# 7seg-2_54-new.net
KiCad netlist of a schematic drawn in EAGLE
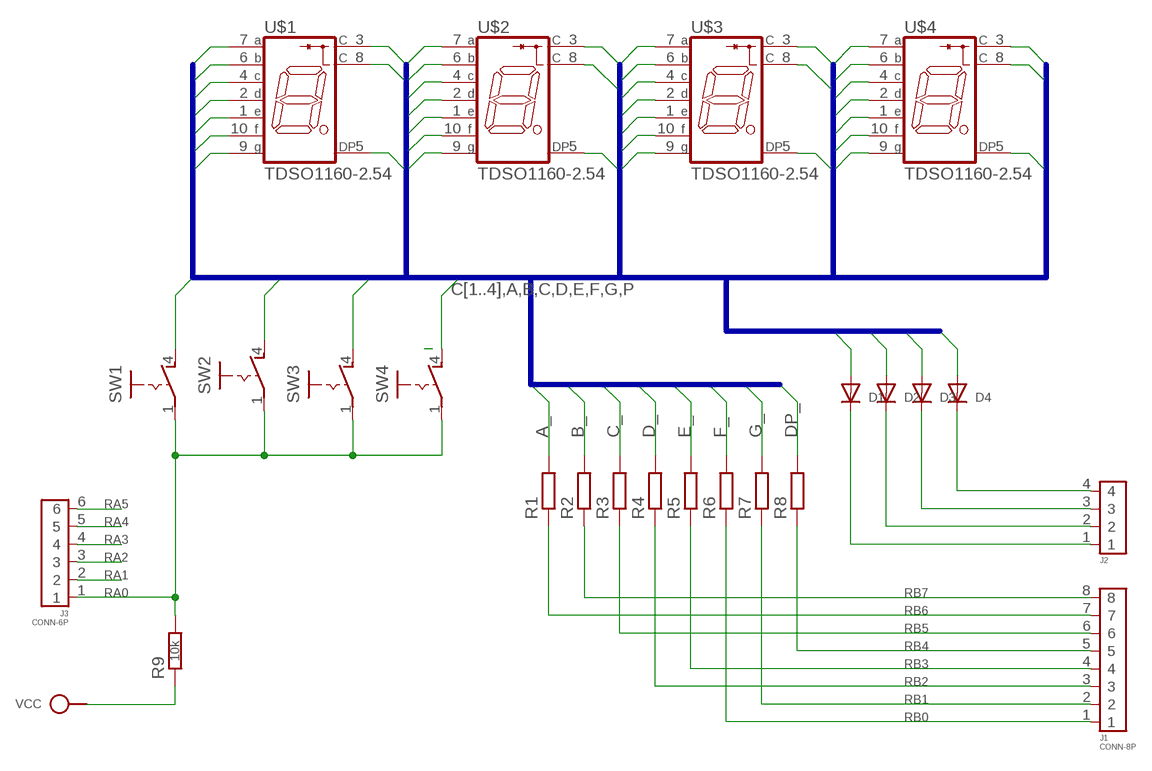
[diagram p0: schematic, sheet 1]

(export (version "E")
  (design (tool "Eeschema 10.0.6"))
  (components
    (comp (ref "D1")
      (value "1N414834-2,5")
      (footprint "eagle-import:DO34-2,5")
      (libsource (lib "eagle-import") (part "1N414834-2,5"))
    )
    (comp (ref "D2")
      (value "1N414834-2,5")
      (footprint "eagle-import:DO34-2,5")
      (libsource (lib "eagle-import") (part "1N414834-2,5"))
    )
    (comp (ref "D3")
      (value "1N414834-2,5")
      (footprint "eagle-import:DO34-2,5")
      (libsource (lib "eagle-import") (part "1N414834-2,5"))
    )
    (comp (ref "D4")
      (value "1N414834-2,5")
      (footprint "eagle-import:DO34-2,5")
      (libsource (lib "eagle-import") (part "1N414834-2,5"))
    )
    (comp (ref "J1")
      (value "CONN-8P")
      (footprint "eagle-import:CONN-8P")
      (libsource (lib "eagle-import") (part "CONN-8P"))
    )
    (comp (ref "J2")
      (value "CONN-4P-4P")
      (footprint "eagle-import:CONN-4P")
      (libsource (lib "eagle-import") (part "CONN-4P-4P"))
    )
    (comp (ref "J3")
      (value "CONN-6P")
      (footprint "eagle-import:CONN-6P")
      (libsource (lib "eagle-import") (part "CONN-6P"))
    )
    (comp (ref "R1")
      (value "R0202/5-V")
      (footprint "eagle-import:0202_5-V")
      (libsource (lib "eagle-import") (part "R0202/5-V"))
    )
    (comp (ref "R2")
      (value "R0202/5-V")
      (footprint "eagle-import:0202_5-V")
      (libsource (lib "eagle-import") (part "R0202/5-V"))
    )
    (comp (ref "R3")
      (value "R0202/5-V")
      (footprint "eagle-import:0202_5-V")
      (libsource (lib "eagle-import") (part "R0202/5-V"))
    )
    (comp (ref "R4")
      (value "R0202/5-V")
      (footprint "eagle-import:0202_5-V")
      (libsource (lib "eagle-import") (part "R0202/5-V"))
    )
    (comp (ref "R5")
      (value "R0202/5-V")
      (footprint "eagle-import:0202_5-V")
      (libsource (lib "eagle-import") (part "R0202/5-V"))
    )
    (comp (ref "R6")
      (value "R0202/5-V")
      (footprint "eagle-import:0202_5-V")
      (libsource (lib "eagle-import") (part "R0202/5-V"))
    )
    (comp (ref "R7")
      (value "R0202/5-V")
      (footprint "eagle-import:0202_5-V")
      (libsource (lib "eagle-import") (part "R0202/5-V"))
    )
    (comp (ref "R8")
      (value "R0202/5-V")
      (footprint "eagle-import:0202_5-V")
      (libsource (lib "eagle-import") (part "R0202/5-V"))
    )
    (comp (ref "R9")
      (value "10k")
      (footprint "eagle-import:0202_5-V")
      (libsource (lib "eagle-import") (part "R0202/5-V"))
    )
    (comp (ref "SW1")
      (value "PB-1P-1T2P1T-2X3")
      (footprint "eagle-import:PB-2P1T-2X3")
      (libsource (lib "eagle-import") (part "PB-1P-1T2P1T-2X3"))
    )
    (comp (ref "SW2")
      (value "PB-1P-1T2P1T-2X3")
      (footprint "eagle-import:PB-2P1T-2X3")
      (libsource (lib "eagle-import") (part "PB-1P-1T2P1T-2X3"))
    )
    (comp (ref "SW3")
      (value "PB-1P-1T2P1T-2X3")
      (footprint "eagle-import:PB-2P1T-2X3")
      (libsource (lib "eagle-import") (part "PB-1P-1T2P1T-2X3"))
    )
    (comp (ref "SW4")
      (value "PB-1P-1T2P1T-2X3")
      (footprint "eagle-import:PB-2P1T-2X3")
      (libsource (lib "eagle-import") (part "PB-1P-1T2P1T-2X3"))
    )
    (comp (ref "U$1")
      (value "TDSO1160-2.54")
      (footprint "eagle-import:TDSX1150-2.54")
      (libsource (lib "eagle-import") (part "TDSO1160-2.54"))
    )
    (comp (ref "U$2")
      (value "TDSO1160-2.54")
      (footprint "eagle-import:TDSX1150-2.54")
      (libsource (lib "eagle-import") (part "TDSO1160-2.54"))
    )
    (comp (ref "U$3")
      (value "TDSO1160-2.54")
      (footprint "eagle-import:TDSX1150-2.54")
      (libsource (lib "eagle-import") (part "TDSO1160-2.54"))
    )
    (comp (ref "U$4")
      (value "TDSO1160-2.54")
      (footprint "eagle-import:TDSX1150-2.54")
      (libsource (lib "eagle-import") (part "TDSO1160-2.54"))
    )
    (comp (ref "VCC")
      (value "SPAD")
      (footprint "eagle-import:SPAD")
      (libsource (lib "eagle-import") (part "SPAD"))
    )
  )
  (nets
    (net (code "9") (name "/A_") (class "Default")
      (node (ref "R1") (pin "2") (pinfunction "2_2") (pintype "passive"))
      (node (ref "U$1") (pin "7") (pinfunction "A_7") (pintype "passive"))
      (node (ref "U$2") (pin "7") (pinfunction "A_7") (pintype "passive"))
      (node (ref "U$3") (pin "7") (pinfunction "A_7") (pintype "passive"))
      (node (ref "U$4") (pin "7") (pinfunction "A_7") (pintype "passive"))
    )
    (net (code "10") (name "/B_") (class "Default")
      (node (ref "R2") (pin "2") (pinfunction "2_2") (pintype "passive"))
      (node (ref "U$1") (pin "6") (pinfunction "B_6") (pintype "passive"))
      (node (ref "U$2") (pin "6") (pinfunction "B_6") (pintype "passive"))
      (node (ref "U$3") (pin "6") (pinfunction "B_6") (pintype "passive"))
      (node (ref "U$4") (pin "6") (pinfunction "B_6") (pintype "passive"))
    )
    (net (code "11") (name "/C1") (class "Default")
      (node (ref "D1") (pin "A") (pinfunction "A_A") (pintype "passive"))
      (node (ref "SW1") (pin "4") (pinfunction "S_4") (pintype "passive"))
      (node (ref "U$1") (pin "3") (pinfunction "C_3") (pintype "passive"))
      (node (ref "U$1") (pin "8") (pinfunction "C_8") (pintype "passive"))
    )
    (net (code "12") (name "/C2") (class "Default")
      (node (ref "D2") (pin "A") (pinfunction "A_A") (pintype "passive"))
      (node (ref "SW2") (pin "4") (pinfunction "S_4") (pintype "passive"))
      (node (ref "U$2") (pin "3") (pinfunction "C_3") (pintype "passive"))
      (node (ref "U$2") (pin "8") (pinfunction "C_8") (pintype "passive"))
    )
    (net (code "13") (name "/C3") (class "Default")
      (node (ref "D3") (pin "A") (pinfunction "A_A") (pintype "passive"))
      (node (ref "SW3") (pin "4") (pinfunction "S_4") (pintype "passive"))
      (node (ref "U$3") (pin "3") (pinfunction "C_3") (pintype "passive"))
      (node (ref "U$3") (pin "8") (pinfunction "C_8") (pintype "passive"))
    )
    (net (code "14") (name "/C4") (class "Default")
      (node (ref "D4") (pin "A") (pinfunction "A_A") (pintype "passive"))
      (node (ref "SW4") (pin "4") (pinfunction "S_4") (pintype "passive"))
      (node (ref "U$4") (pin "3") (pinfunction "C_3") (pintype "passive"))
      (node (ref "U$4") (pin "8") (pinfunction "C_8") (pintype "passive"))
    )
    (net (code "15") (name "/C_") (class "Default")
      (node (ref "R3") (pin "2") (pinfunction "2_2") (pintype "passive"))
      (node (ref "U$1") (pin "4") (pinfunction "C_4") (pintype "passive"))
      (node (ref "U$2") (pin "4") (pinfunction "C_4") (pintype "passive"))
      (node (ref "U$3") (pin "4") (pinfunction "C_4") (pintype "passive"))
      (node (ref "U$4") (pin "4") (pinfunction "C_4") (pintype "passive"))
    )
    (net (code "16") (name "/DP_") (class "Default")
      (node (ref "R8") (pin "2") (pinfunction "2_2") (pintype "passive"))
      (node (ref "U$1") (pin "5") (pinfunction "DP_5") (pintype "passive"))
      (node (ref "U$2") (pin "5") (pinfunction "DP_5") (pintype "passive"))
      (node (ref "U$3") (pin "5") (pinfunction "DP_5") (pintype "passive"))
      (node (ref "U$4") (pin "5") (pinfunction "DP_5") (pintype "passive"))
    )
    (net (code "17") (name "/D_") (class "Default")
      (node (ref "R4") (pin "2") (pinfunction "2_2") (pintype "passive"))
      (node (ref "U$1") (pin "2") (pinfunction "D_2") (pintype "passive"))
      (node (ref "U$2") (pin "2") (pinfunction "D_2") (pintype "passive"))
      (node (ref "U$3") (pin "2") (pinfunction "D_2") (pintype "passive"))
      (node (ref "U$4") (pin "2") (pinfunction "D_2") (pintype "passive"))
    )
    (net (code "18") (name "/E_") (class "Default")
      (node (ref "R5") (pin "2") (pinfunction "2_2") (pintype "passive"))
      (node (ref "U$1") (pin "1") (pinfunction "E_1") (pintype "passive"))
      (node (ref "U$2") (pin "1") (pinfunction "E_1") (pintype "passive"))
      (node (ref "U$3") (pin "1") (pinfunction "E_1") (pintype "passive"))
      (node (ref "U$4") (pin "1") (pinfunction "E_1") (pintype "passive"))
    )
    (net (code "19") (name "/F_") (class "Default")
      (node (ref "R6") (pin "2") (pinfunction "2_2") (pintype "passive"))
      (node (ref "U$1") (pin "10") (pinfunction "F_10") (pintype "passive"))
      (node (ref "U$2") (pin "10") (pinfunction "F_10") (pintype "passive"))
      (node (ref "U$3") (pin "10") (pinfunction "F_10") (pintype "passive"))
      (node (ref "U$4") (pin "10") (pinfunction "F_10") (pintype "passive"))
    )
    (net (code "20") (name "/G_") (class "Default")
      (node (ref "R7") (pin "2") (pinfunction "2_2") (pintype "passive"))
      (node (ref "U$1") (pin "9") (pinfunction "G_9") (pintype "passive"))
      (node (ref "U$2") (pin "9") (pinfunction "G_9") (pintype "passive"))
      (node (ref "U$3") (pin "9") (pinfunction "G_9") (pintype "passive"))
      (node (ref "U$4") (pin "9") (pinfunction "G_9") (pintype "passive"))
    )
    (net (code "21") (name "/RA0") (class "Default")
      (node (ref "J3") (pin "1") (pinfunction "1_1") (pintype "passive"))
      (node (ref "R9") (pin "2") (pinfunction "2_2") (pintype "passive"))
      (node (ref "SW1") (pin "1") (pinfunction "P_1") (pintype "passive"))
      (node (ref "SW2") (pin "1") (pinfunction "P_1") (pintype "passive"))
      (node (ref "SW3") (pin "1") (pinfunction "P_1") (pintype "passive"))
      (node (ref "SW4") (pin "1") (pinfunction "P_1") (pintype "passive"))
    )
    (net (code "22") (name "/RA1") (class "Default")
      (node (ref "J3") (pin "2") (pinfunction "2_2") (pintype "passive"))
    )
    (net (code "23") (name "/RA2") (class "Default")
      (node (ref "J3") (pin "3") (pinfunction "3_3") (pintype "passive"))
    )
    (net (code "24") (name "/RA3") (class "Default")
      (node (ref "J3") (pin "4") (pinfunction "4_4") (pintype "passive"))
    )
    (net (code "25") (name "/RA4") (class "Default")
      (node (ref "J3") (pin "5") (pinfunction "5_5") (pintype "passive"))
    )
    (net (code "26") (name "/RA5") (class "Default")
      (node (ref "J3") (pin "6") (pinfunction "6_6") (pintype "passive"))
    )
    (net (code "27") (name "/RB0") (class "Default")
      (node (ref "J1") (pin "1") (pinfunction "1_1") (pintype "passive"))
      (node (ref "R6") (pin "1") (pinfunction "1_1") (pintype "passive"))
    )
    (net (code "28") (name "/RB1") (class "Default")
      (node (ref "J1") (pin "2") (pinfunction "2_2") (pintype "passive"))
      (node (ref "R7") (pin "1") (pinfunction "1_1") (pintype "passive"))
    )
    (net (code "29") (name "/RB2") (class "Default")
      (node (ref "J1") (pin "3") (pinfunction "3_3") (pintype "passive"))
      (node (ref "R4") (pin "1") (pinfunction "1_1") (pintype "passive"))
    )
    (net (code "30") (name "/RB3") (class "Default")
      (node (ref "J1") (pin "4") (pinfunction "4_4") (pintype "passive"))
      (node (ref "R5") (pin "1") (pinfunction "1_1") (pintype "passive"))
    )
    (net (code "31") (name "/RB4") (class "Default")
      (node (ref "J1") (pin "5") (pinfunction "5_5") (pintype "passive"))
      (node (ref "R8") (pin "1") (pinfunction "1_1") (pintype "passive"))
    )
    (net (code "32") (name "/RB5") (class "Default")
      (node (ref "J1") (pin "6") (pinfunction "6_6") (pintype "passive"))
      (node (ref "R3") (pin "1") (pinfunction "1_1") (pintype "passive"))
    )
    (net (code "33") (name "/RB6") (class "Default")
      (node (ref "J1") (pin "7") (pinfunction "7_7") (pintype "passive"))
      (node (ref "R1") (pin "1") (pinfunction "1_1") (pintype "passive"))
    )
    (net (code "34") (name "/RB7") (class "Default")
      (node (ref "J1") (pin "8") (pinfunction "8_8") (pintype "passive"))
      (node (ref "R2") (pin "1") (pinfunction "1_1") (pintype "passive"))
    )
    (net (code "36") (name "Net-(D1-PadC)") (class "Default")
      (node (ref "D1") (pin "C") (pinfunction "C_C") (pintype "passive"))
      (node (ref "J2") (pin "1") (pinfunction "1_1") (pintype "bidirectional"))
    )
    (net (code "37") (name "Net-(D2-PadC)") (class "Default")
      (node (ref "D2") (pin "C") (pinfunction "C_C") (pintype "passive"))
      (node (ref "J2") (pin "2") (pinfunction "2_2") (pintype "bidirectional"))
    )
    (net (code "38") (name "Net-(D3-PadC)") (class "Default")
      (node (ref "D3") (pin "C") (pinfunction "C_C") (pintype "passive"))
      (node (ref "J2") (pin "3") (pinfunction "3_3") (pintype "bidirectional"))
    )
    (net (code "39") (name "Net-(D4-PadC)") (class "Default")
      (node (ref "D4") (pin "C") (pinfunction "C_C") (pintype "passive"))
      (node (ref "J2") (pin "4") (pinfunction "4_4") (pintype "bidirectional"))
    )
    (net (code "40") (name "Net-(VCC-P$1)") (class "Default")
      (node (ref "R9") (pin "1") (pinfunction "1_1") (pintype "passive"))
      (node (ref "VCC") (pin "1") (pinfunction "P$1_1") (pintype "passive"))
    )
  )
)
